# KDWM1000_Sch.net
KiCad netlist of a schematic drawn in Altium Designer
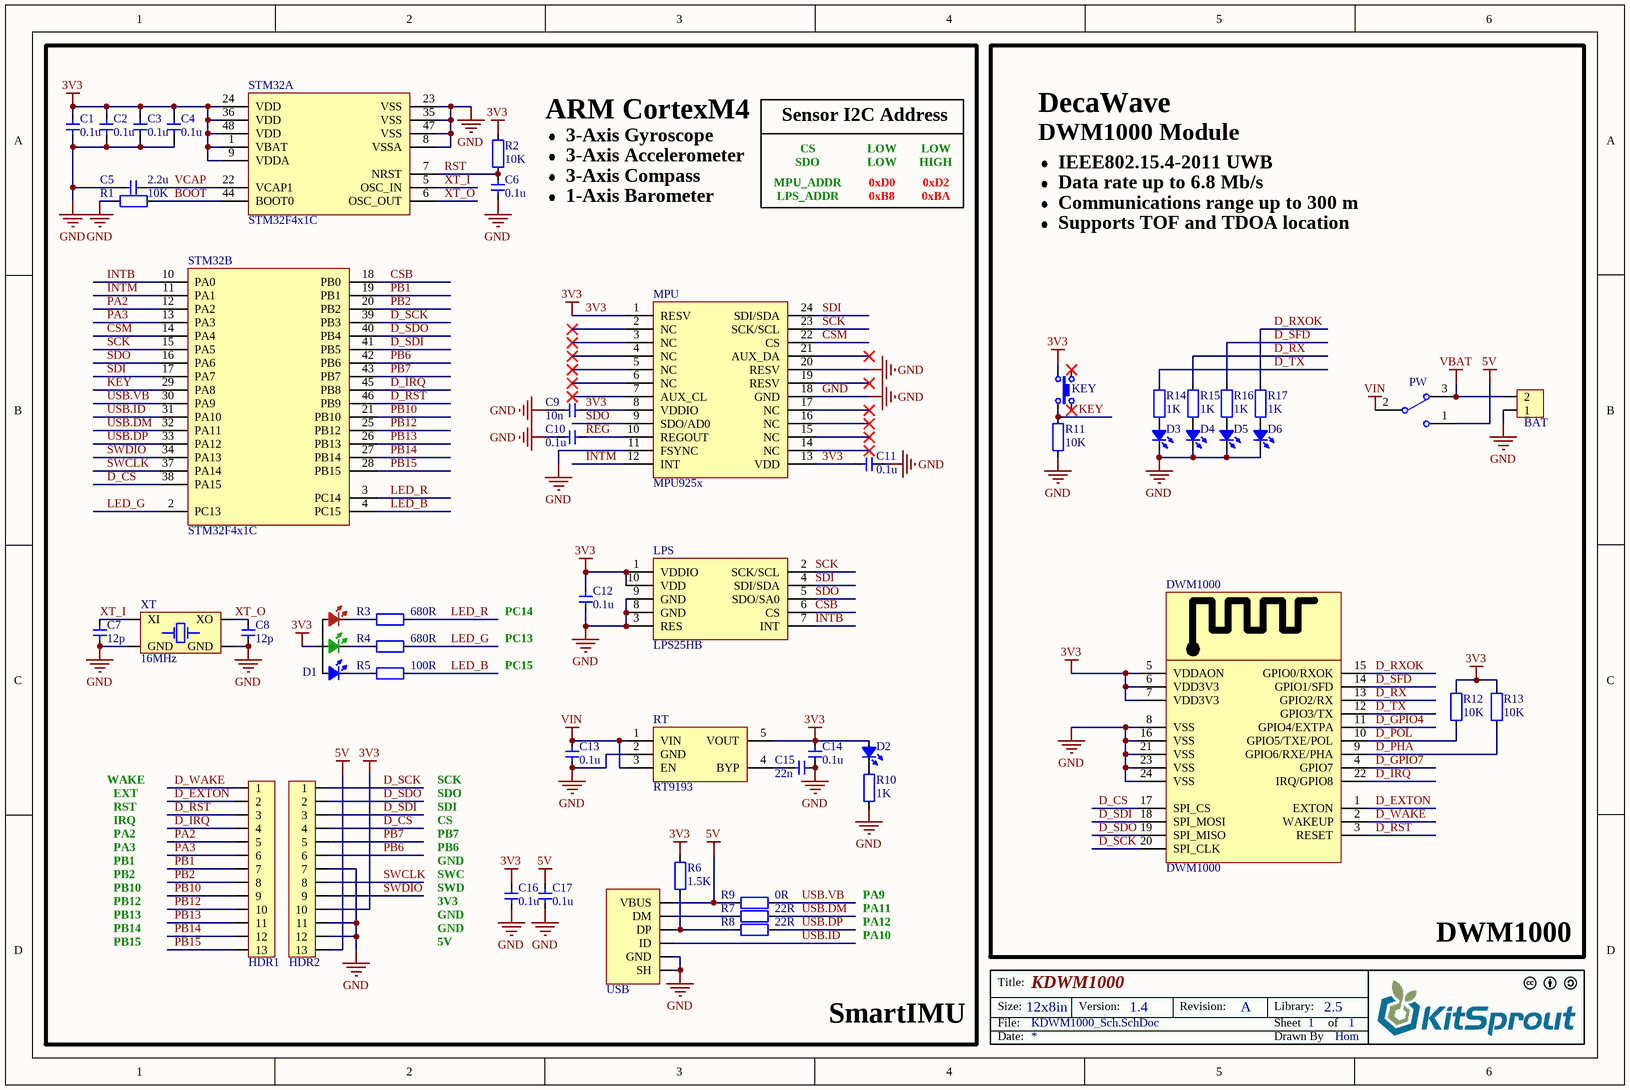
[diagram p0: KDWM1000_Sch.SchDoc]

(export (version "E")
  (design (tool "Eeschema 10.0.6"))
  (components
    (comp (ref "BAT")
      (value "HDR1x2_2.54")
      (footprint "PCB_ConnectorHDR:HDR1X2_2.54_180HD")
      (description "Header")
      (libsource (lib "SCH_ConnectorHDR") (part "HDR1x2_2.54T"))
    )
    (comp (ref "C1")
      (value "0.1u")
      (footprint "PCB_PassiveCap:CAP_0402")
      (description "Capacitor")
      (fields (field (name "Comment") "Cap_0402"))
      (libsource (lib "SCH_Passive") (part "Cap_0402"))
    )
    (comp (ref "C2")
      (value "0.1u")
      (footprint "PCB_PassiveCap:CAP_0402")
      (description "Capacitor")
      (fields (field (name "Comment") "Cap_0402"))
      (libsource (lib "SCH_Passive") (part "Cap_0402"))
    )
    (comp (ref "C3")
      (value "0.1u")
      (footprint "PCB_PassiveCap:CAP_0402")
      (description "Capacitor")
      (fields (field (name "Comment") "Cap_0402"))
      (libsource (lib "SCH_Passive") (part "Cap_0402"))
    )
    (comp (ref "C4")
      (value "0.1u")
      (footprint "PCB_PassiveCap:CAP_0402")
      (description "Capacitor")
      (fields (field (name "Comment") "Cap_0402"))
      (libsource (lib "SCH_Passive") (part "Cap_0402"))
    )
    (comp (ref "C5")
      (value "2.2u")
      (footprint "PCB_PassiveCap:CAP_0402")
      (description "Capacitor")
      (fields (field (name "Comment") "Cap_0402"))
      (libsource (lib "SCH_Passive") (part "Cap_0402"))
    )
    (comp (ref "C6")
      (value "0.1u")
      (footprint "PCB_PassiveCap:CAP_0402")
      (description "Capacitor")
      (fields (field (name "Comment") "Cap_0402"))
      (libsource (lib "SCH_Passive") (part "Cap_0402"))
    )
    (comp (ref "C7")
      (value "12p")
      (footprint "PCB_PassiveCap:CAP_0402")
      (description "Capacitor")
      (fields (field (name "Comment") "Cap_0402"))
      (libsource (lib "SCH_Passive") (part "Cap_0402"))
    )
    (comp (ref "C8")
      (value "12p")
      (footprint "PCB_PassiveCap:CAP_0402")
      (description "Capacitor")
      (fields (field (name "Comment") "Cap_0402"))
      (libsource (lib "SCH_Passive") (part "Cap_0402"))
    )
    (comp (ref "C9")
      (value "10n")
      (footprint "PCB_PassiveCap:CAP_0402")
      (description "Capacitor")
      (fields (field (name "Comment") "Cap_0402"))
      (libsource (lib "SCH_Passive") (part "Cap_0402"))
    )
    (comp (ref "C10")
      (value "0.1u")
      (footprint "PCB_PassiveCap:CAP_0402")
      (description "Capacitor")
      (fields (field (name "Comment") "Cap_0402"))
      (libsource (lib "SCH_Passive") (part "Cap_0402"))
    )
    (comp (ref "C11")
      (value "0.1u")
      (footprint "PCB_PassiveCap:CAP_0402")
      (description "Capacitor")
      (fields (field (name "Comment") "Cap_0402"))
      (libsource (lib "SCH_Passive") (part "Cap_0402"))
    )
    (comp (ref "C12")
      (value "0.1u")
      (footprint "PCB_PassiveCap:CAP_0402")
      (description "Capacitor")
      (fields (field (name "Comment") "Cap_0402"))
      (libsource (lib "SCH_Passive") (part "Cap_0402"))
    )
    (comp (ref "C13")
      (value "0.1u")
      (footprint "PCB_PassiveCap:CAP_0603")
      (description "Capacitor")
      (fields (field (name "Comment") "Cap_0603"))
      (libsource (lib "SCH_Passive") (part "Cap_0603"))
    )
    (comp (ref "C14")
      (value "0.1u")
      (footprint "PCB_PassiveCap:CAP_0603")
      (description "Capacitor")
      (fields (field (name "Comment") "Cap_0603"))
      (libsource (lib "SCH_Passive") (part "Cap_0603"))
    )
    (comp (ref "C15")
      (value "22n")
      (footprint "PCB_PassiveCap:CAP_0603")
      (description "Capacitor")
      (fields (field (name "Comment") "Cap_0603"))
      (libsource (lib "SCH_Passive") (part "Cap_0603"))
    )
    (comp (ref "C16")
      (value "0.1u")
      (footprint "PCB_PassiveCap:CAP_0603")
      (description "Capacitor")
      (fields (field (name "Comment") "Cap_0603"))
      (libsource (lib "SCH_Passive") (part "Cap_0603"))
    )
    (comp (ref "C17")
      (value "0.1u")
      (footprint "PCB_PassiveCap:CAP_0603")
      (description "Capacitor")
      (fields (field (name "Comment") "Cap_0603"))
      (libsource (lib "SCH_Passive") (part "Cap_0603"))
    )
    (comp (ref "D1")
      (value "LED_1616_RGB")
      (footprint "PCB_ActiveLED:LED_1616_RGB")
      (description "LED")
      (libsource (lib "SCH_Active") (part "LED_1616_RGB"))
    )
    (comp (ref "D2")
      (value "LED_0603")
      (footprint "PCB_ActiveLED:LED_0603_YELLOW")
      (description "LED")
      (libsource (lib "SCH_Active") (part "LED_0603"))
    )
    (comp (ref "D3")
      (value "LED_0603")
      (footprint "PCB_ActiveLED:LED_0603_YELLOW")
      (description "LED")
      (libsource (lib "SCH_Active") (part "LED_0603"))
    )
    (comp (ref "D4")
      (value "LED_0603")
      (footprint "PCB_ActiveLED:LED_0603_YELLOW")
      (description "LED")
      (libsource (lib "SCH_Active") (part "LED_0603"))
    )
    (comp (ref "D5")
      (value "LED_0603")
      (footprint "PCB_ActiveLED:LED_0603_RED")
      (description "LED")
      (libsource (lib "SCH_Active") (part "LED_0603"))
    )
    (comp (ref "D6")
      (value "LED_0603")
      (footprint "PCB_ActiveLED:LED_0603_GREEN")
      (description "LED")
      (libsource (lib "SCH_Active") (part "LED_0603"))
    )
    (comp (ref "DWM1000")
      (value "DWM1000")
      (footprint "PCB_Module:DWM1000")
      (description "Module")
      (fields (field (name "MANUFACTURER") "Decawave Limited"))
      (libsource (lib "SCH_Module") (part "DWM1000"))
    )
    (comp (ref "HDR1")
      (value "HDR1x13_2.54")
      (footprint "PCB_ConnectorHDR:HDR1X13_2.54_180")
      (description "Header")
      (libsource (lib "SCH_ConnectorHDR") (part "HDR1x13_2.54"))
    )
    (comp (ref "HDR2")
      (value "HDR1x13_2.54T")
      (footprint "PCB_ConnectorHDR:HDR1X13_2.54_180")
      (description "Header")
      (libsource (lib "SCH_ConnectorHDR") (part "HDR1x13_2.54T"))
    )
    (comp (ref "KEY")
      (value "ButtonTACT")
      (footprint "PCB_Switch:ButtonTACT_3.5*3.55_90")
      (description "Button")
      (libsource (lib "SCH_Switch") (part "ButtonTACT"))
    )
    (comp (ref "LPS")
      (value "LPS25HB")
      (footprint "PCB_IntegratedCircuit:HCLGA-2.5x2.5_10")
      (description "Sensor Pressure")
      (libsource (lib "SCH_IntegratedCircuit") (part "LPS25Hx"))
    )
    (comp (ref "MPU")
      (value "MPU925x")
      (footprint "PCB_IntegratedCircuit:QFN_P0.4_24")
      (description "Sensor Motion")
      (libsource (lib "SCH_IntegratedCircuit") (part "MPU925x"))
    )
    (comp (ref "PW")
      (value "SwitchSPDT_2.8x6.6_90")
      (footprint "PCB_Switch:SwitchSPDT_2.8X6.6_90")
      (description "Switch")
      (libsource (lib "SCH_Switch") (part "SwitchSPDT_2.8x6.6_90"))
    )
    (comp (ref "R1")
      (value "10K")
      (footprint "PCB_PassiveRes:RES_0402")
      (description "Resistor")
      (fields (field (name "Comment") "Res_0402"))
      (libsource (lib "") (part "Res_0402_2"))
    )
    (comp (ref "R2")
      (value "10K")
      (footprint "PCB_PassiveRes:RES_0402")
      (description "Resistor")
      (fields (field (name "Comment") "Res_0402"))
      (libsource (lib "") (part "Res_0402_1"))
    )
    (comp (ref "R3")
      (value "680R")
      (footprint "PCB_PassiveRes:RES_0402")
      (description "Resistor")
      (fields (field (name "Comment") "Res_0402"))
      (libsource (lib "SCH_Passive") (part "Res_0402"))
    )
    (comp (ref "R4")
      (value "680R")
      (footprint "PCB_PassiveRes:RES_0402")
      (description "Resistor")
      (fields (field (name "Comment") "Res_0402"))
      (libsource (lib "SCH_Passive") (part "Res_0402"))
    )
    (comp (ref "R5")
      (value "100R")
      (footprint "PCB_PassiveRes:RES_0402")
      (description "Resistor")
      (fields (field (name "Comment") "Res_0402"))
      (libsource (lib "SCH_Passive") (part "Res_0402"))
    )
    (comp (ref "R6")
      (value "1.5K")
      (footprint "PCB_PassiveRes:RES_0603")
      (description "Resistor")
      (fields (field (name "Comment") "Res_0603"))
      (libsource (lib "") (part "Res_0603_2"))
    )
    (comp (ref "R7")
      (value "22R")
      (footprint "PCB_PassiveRes:RES_0603")
      (description "Resistor")
      (fields (field (name "Comment") "Res_0603"))
      (libsource (lib "SCH_Passive") (part "Res_0603"))
    )
    (comp (ref "R8")
      (value "22R")
      (footprint "PCB_PassiveRes:RES_0603")
      (description "Resistor")
      (fields (field (name "Comment") "Res_0603"))
      (libsource (lib "SCH_Passive") (part "Res_0603"))
    )
    (comp (ref "R9")
      (value "0R")
      (footprint "PCB_PassiveRes:RES_0603")
      (description "Resistor")
      (fields (field (name "Comment") "Res_0603"))
      (libsource (lib "") (part "Res_0603_3"))
    )
    (comp (ref "R10")
      (value "1K")
      (footprint "PCB_PassiveRes:RES_0603")
      (description "Resistor")
      (fields (field (name "Comment") "Res_0603"))
      (libsource (lib "") (part "Res_0603_1"))
    )
    (comp (ref "R11")
      (value "10K")
      (footprint "PCB_PassiveRes:RES_0603")
      (description "Resistor")
      (fields (field (name "Comment") "Res_0603"))
      (libsource (lib "") (part "Res_0603_1"))
    )
    (comp (ref "R12")
      (value "10K")
      (footprint "PCB_PassiveRes:RES_0603")
      (description "Resistor")
      (fields (field (name "Comment") "Res_0603"))
      (libsource (lib "") (part "Res_0603_1"))
    )
    (comp (ref "R13")
      (value "10K")
      (footprint "PCB_PassiveRes:RES_0603")
      (description "Resistor")
      (fields (field (name "Comment") "Res_0603"))
      (libsource (lib "") (part "Res_0603_1"))
    )
    (comp (ref "R14")
      (value "1K")
      (footprint "PCB_PassiveRes:RES_0603")
      (description "Resistor")
      (fields (field (name "Comment") "Res_0603"))
      (libsource (lib "") (part "Res_0603_1"))
    )
    (comp (ref "R15")
      (value "1K")
      (footprint "PCB_PassiveRes:RES_0603")
      (description "Resistor")
      (fields (field (name "Comment") "Res_0603"))
      (libsource (lib "") (part "Res_0603_1"))
    )
    (comp (ref "R16")
      (value "1K")
      (footprint "PCB_PassiveRes:RES_0603")
      (description "Resistor")
      (fields (field (name "Comment") "Res_0603"))
      (libsource (lib "") (part "Res_0603_1"))
    )
    (comp (ref "R17")
      (value "1K")
      (footprint "PCB_PassiveRes:RES_0603")
      (description "Resistor")
      (fields (field (name "Comment") "Res_0603"))
      (libsource (lib "") (part "Res_0603_1"))
    )
    (comp (ref "RT")
      (value "RT9193")
      (footprint "PCB_IntegratedCircuit:SOT23-5")
      (description "Power")
      (libsource (lib "SCH_IntegratedCircuit") (part "RT9193"))
    )
    (comp (ref "STM32")
      (value "STM32F4x1C")
      (footprint "PCB_IntegratedCircuit:QFN_P0.5_48")
      (description "MCU")
      (libsource (lib "SCH_IntegratedCircuit") (part "STM32F4x1C"))
    )
    (comp (ref "USB")
      (value "USB_Micro")
      (footprint "PCB_USB:USB_Micro-AB")
      (description "USB")
      (libsource (lib "SCH_USB") (part "USB_Micro"))
    )
    (comp (ref "XT")
      (value "16MHz")
      (footprint "PCB_Oscillator:XT_2520_4")
      (description "Crystal Oscillator")
      (fields (field (name "Comment") "XTAL_2520_4P"))
      (libsource (lib "SCH_Oscillator") (part "XTAL_2520_4P"))
    )
  )
  (nets
    (net (code "1") (name "/BOOT") (class "Default")
      (node (ref "R1") (pin "2") (pinfunction "2_2") (pintype "passive"))
      (node (ref "STM32") (pin "44") (pinfunction "BOOT0_44") (pintype "passive"))
    )
    (net (code "2") (name "/CSB") (class "Default")
      (node (ref "LPS") (pin "6") (pinfunction "CS_6") (pintype "passive"))
      (node (ref "STM32") (pin "18") (pinfunction "PB0_18") (pintype "passive"))
    )
    (net (code "3") (name "/CSM") (class "Default")
      (node (ref "MPU") (pin "22") (pinfunction "CS_22") (pintype "passive"))
      (node (ref "STM32") (pin "14") (pinfunction "PA4_14") (pintype "passive"))
    )
    (net (code "4") (name "/D_CS") (class "Default")
      (node (ref "DWM1000") (pin "17") (pinfunction "SPI_CS_17") (pintype "passive"))
      (node (ref "HDR2") (pin "4") (pinfunction "4_4") (pintype "passive"))
      (node (ref "STM32") (pin "38") (pinfunction "PA15_38") (pintype "passive"))
    )
    (net (code "5") (name "/D_EXTON") (class "Default")
      (node (ref "DWM1000") (pin "1") (pinfunction "EXTON_1") (pintype "passive"))
      (node (ref "HDR1") (pin "2") (pinfunction "2_2") (pintype "passive"))
    )
    (net (code "6") (name "/D_GPIO4") (class "Default")
      (node (ref "DWM1000") (pin "11") (pinfunction "GPIO4/EXTPA_11") (pintype "passive"))
    )
    (net (code "7") (name "/D_GPIO7") (class "Default")
      (node (ref "DWM1000") (pin "4") (pinfunction "GPIO7_4") (pintype "passive"))
    )
    (net (code "8") (name "/D_IRQ") (class "Default")
      (node (ref "DWM1000") (pin "22") (pinfunction "IRQ/GPIO8_22") (pintype "passive"))
      (node (ref "HDR1") (pin "4") (pinfunction "4_4") (pintype "passive"))
      (node (ref "STM32") (pin "45") (pinfunction "PB8_45") (pintype "passive"))
    )
    (net (code "9") (name "/D_PHA") (class "Default")
      (node (ref "DWM1000") (pin "9") (pinfunction "GPIO6/RXE/PHA_9") (pintype "passive"))
      (node (ref "R13") (pin "1") (pinfunction "1_1") (pintype "passive"))
    )
    (net (code "10") (name "/D_POL") (class "Default")
      (node (ref "DWM1000") (pin "10") (pinfunction "GPIO5/TXE/POL_10") (pintype "passive"))
      (node (ref "R12") (pin "1") (pinfunction "1_1") (pintype "passive"))
    )
    (net (code "11") (name "/D_RST") (class "Default")
      (node (ref "DWM1000") (pin "3") (pinfunction "RESET_3") (pintype "passive"))
      (node (ref "HDR1") (pin "3") (pinfunction "3_3") (pintype "passive"))
      (node (ref "STM32") (pin "46") (pinfunction "PB9_46") (pintype "passive"))
    )
    (net (code "12") (name "/D_RX") (class "Default")
      (node (ref "DWM1000") (pin "13") (pinfunction "GPIO2/RX_13") (pintype "passive"))
      (node (ref "R15") (pin "2") (pinfunction "2_2") (pintype "passive"))
    )
    (net (code "13") (name "/D_RXOK") (class "Default")
      (node (ref "DWM1000") (pin "15") (pinfunction "GPIO0/RXOK_15") (pintype "passive"))
      (node (ref "R17") (pin "2") (pinfunction "2_2") (pintype "passive"))
    )
    (net (code "14") (name "/D_SCK") (class "Default")
      (node (ref "DWM1000") (pin "20") (pinfunction "SPI_CLK_20") (pintype "passive"))
      (node (ref "HDR2") (pin "1") (pinfunction "1_1") (pintype "passive"))
      (node (ref "STM32") (pin "39") (pinfunction "PB3_39") (pintype "passive"))
    )
    (net (code "15") (name "/D_SDI") (class "Default")
      (node (ref "DWM1000") (pin "18") (pinfunction "SPI_MOSI_18") (pintype "passive"))
      (node (ref "HDR2") (pin "3") (pinfunction "3_3") (pintype "passive"))
      (node (ref "STM32") (pin "41") (pinfunction "PB5_41") (pintype "passive"))
    )
    (net (code "16") (name "/D_SDO") (class "Default")
      (node (ref "DWM1000") (pin "19") (pinfunction "SPI_MISO_19") (pintype "passive"))
      (node (ref "HDR2") (pin "2") (pinfunction "2_2") (pintype "passive"))
      (node (ref "STM32") (pin "40") (pinfunction "PB4_40") (pintype "passive"))
    )
    (net (code "17") (name "/D_SFD") (class "Default")
      (node (ref "DWM1000") (pin "14") (pinfunction "GPIO1/SFD_14") (pintype "passive"))
      (node (ref "R16") (pin "2") (pinfunction "2_2") (pintype "passive"))
    )
    (net (code "18") (name "/D_TX") (class "Default")
      (node (ref "DWM1000") (pin "12") (pinfunction "GPIO3/TX_12") (pintype "passive"))
      (node (ref "R14") (pin "2") (pinfunction "2_2") (pintype "passive"))
    )
    (net (code "19") (name "/D_WAKE") (class "Default")
      (node (ref "DWM1000") (pin "2") (pinfunction "WAKEUP_2") (pintype "passive"))
      (node (ref "HDR1") (pin "1") (pinfunction "1_1") (pintype "passive"))
    )
    (net (code "20") (name "/INTB") (class "Default")
      (node (ref "LPS") (pin "7") (pinfunction "INT_7") (pintype "passive"))
      (node (ref "STM32") (pin "10") (pinfunction "PA0_10") (pintype "passive"))
    )
    (net (code "21") (name "/INTM") (class "Default")
      (node (ref "MPU") (pin "12") (pinfunction "INT_12") (pintype "passive"))
      (node (ref "STM32") (pin "11") (pinfunction "PA1_11") (pintype "passive"))
    )
    (net (code "22") (name "/KEY") (class "Default")
      (node (ref "KEY") (pin "4") (pinfunction "4_4") (pintype "passive"))
      (node (ref "R11") (pin "2") (pinfunction "2_2") (pintype "passive"))
      (node (ref "STM32") (pin "29") (pinfunction "PA8_29") (pintype "passive"))
    )
    (net (code "23") (name "/LED_B") (class "Default")
      (node (ref "R5") (pin "1") (pinfunction "1_1") (pintype "passive"))
      (node (ref "STM32") (pin "4") (pinfunction "PC15_4") (pintype "passive"))
    )
    (net (code "24") (name "/LED_G") (class "Default")
      (node (ref "R4") (pin "1") (pinfunction "1_1") (pintype "passive"))
      (node (ref "STM32") (pin "2") (pinfunction "PC13_2") (pintype "passive"))
    )
    (net (code "25") (name "/LED_R") (class "Default")
      (node (ref "R3") (pin "1") (pinfunction "1_1") (pintype "passive"))
      (node (ref "STM32") (pin "3") (pinfunction "PC14_3") (pintype "passive"))
    )
    (net (code "26") (name "/PA2") (class "Default")
      (node (ref "HDR1") (pin "5") (pinfunction "5_5") (pintype "passive"))
      (node (ref "STM32") (pin "12") (pinfunction "PA2_12") (pintype "passive"))
    )
    (net (code "27") (name "/PA3") (class "Default")
      (node (ref "HDR1") (pin "6") (pinfunction "6_6") (pintype "passive"))
      (node (ref "STM32") (pin "13") (pinfunction "PA3_13") (pintype "passive"))
    )
    (net (code "28") (name "/PB1") (class "Default")
      (node (ref "HDR1") (pin "7") (pinfunction "7_7") (pintype "passive"))
      (node (ref "STM32") (pin "19") (pinfunction "PB1_19") (pintype "passive"))
    )
    (net (code "29") (name "/PB2") (class "Default")
      (node (ref "HDR1") (pin "8") (pinfunction "8_8") (pintype "passive"))
      (node (ref "STM32") (pin "20") (pinfunction "PB2_20") (pintype "passive"))
    )
    (net (code "30") (name "/PB6") (class "Default")
      (node (ref "HDR2") (pin "6") (pinfunction "6_6") (pintype "passive"))
      (node (ref "STM32") (pin "42") (pinfunction "PB6_42") (pintype "passive"))
    )
    (net (code "31") (name "/PB7") (class "Default")
      (node (ref "HDR2") (pin "5") (pinfunction "5_5") (pintype "passive"))
      (node (ref "STM32") (pin "43") (pinfunction "PB7_43") (pintype "passive"))
    )
    (net (code "32") (name "/PB10") (class "Default")
      (node (ref "HDR1") (pin "9") (pinfunction "9_9") (pintype "passive"))
      (node (ref "STM32") (pin "21") (pinfunction "PB10_21") (pintype "passive"))
    )
    (net (code "33") (name "/PB12") (class "Default")
      (node (ref "HDR1") (pin "10") (pinfunction "10_10") (pintype "passive"))
      (node (ref "STM32") (pin "25") (pinfunction "PB12_25") (pintype "passive"))
    )
    (net (code "34") (name "/PB13") (class "Default")
      (node (ref "HDR1") (pin "11") (pinfunction "11_11") (pintype "passive"))
      (node (ref "STM32") (pin "26") (pinfunction "PB13_26") (pintype "passive"))
    )
    (net (code "35") (name "/PB14") (class "Default")
      (node (ref "HDR1") (pin "12") (pinfunction "12_12") (pintype "passive"))
      (node (ref "STM32") (pin "27") (pinfunction "PB14_27") (pintype "passive"))
    )
    (net (code "36") (name "/PB15") (class "Default")
      (node (ref "HDR1") (pin "13") (pinfunction "13_13") (pintype "passive"))
      (node (ref "STM32") (pin "28") (pinfunction "PB15_28") (pintype "passive"))
    )
    (net (code "37") (name "/REG") (class "Default")
      (node (ref "C10") (pin "1") (pinfunction "1_1") (pintype "passive"))
      (node (ref "MPU") (pin "10") (pinfunction "REGOUT_10") (pintype "passive"))
    )
    (net (code "38") (name "/RST") (class "Default")
      (node (ref "C6") (pin "1") (pinfunction "1_1") (pintype "passive"))
      (node (ref "R2") (pin "1") (pinfunction "1_1") (pintype "passive"))
      (node (ref "STM32") (pin "7") (pinfunction "NRST_7") (pintype "passive"))
    )
    (net (code "39") (name "/SCK") (class "Default")
      (node (ref "LPS") (pin "2") (pinfunction "SCK/SCL_2") (pintype "passive"))
      (node (ref "MPU") (pin "23") (pinfunction "SCK/SCL_23") (pintype "passive"))
      (node (ref "STM32") (pin "15") (pinfunction "PA5_15") (pintype "passive"))
    )
    (net (code "40") (name "/SDI") (class "Default")
      (node (ref "LPS") (pin "4") (pinfunction "SDI/SDA_4") (pintype "passive"))
      (node (ref "MPU") (pin "24") (pinfunction "SDI/SDA_24") (pintype "passive"))
      (node (ref "STM32") (pin "17") (pinfunction "PA7_17") (pintype "passive"))
    )
    (net (code "41") (name "/SDO") (class "Default")
      (node (ref "LPS") (pin "5") (pinfunction "SDO/SA0_5") (pintype "passive"))
      (node (ref "MPU") (pin "9") (pinfunction "SDO/AD0_9") (pintype "passive"))
      (node (ref "STM32") (pin "16") (pinfunction "PA6_16") (pintype "passive"))
    )
    (net (code "42") (name "/SWCLK") (class "Default")
      (node (ref "HDR2") (pin "8") (pinfunction "8_8") (pintype "passive"))
      (node (ref "STM32") (pin "37") (pinfunction "PA14_37") (pintype "passive"))
    )
    (net (code "43") (name "/SWDIO") (class "Default")
      (node (ref "HDR2") (pin "9") (pinfunction "9_9") (pintype "passive"))
      (node (ref "STM32") (pin "34") (pinfunction "PA13_34") (pintype "passive"))
    )
    (net (code "44") (name "/USB.DM") (class "Default")
      (node (ref "R7") (pin "2") (pinfunction "2_2") (pintype "passive"))
      (node (ref "STM32") (pin "32") (pinfunction "PA11_32") (pintype "passive"))
    )
    (net (code "45") (name "/USB.DP") (class "Default")
      (node (ref "R8") (pin "2") (pinfunction "2_2") (pintype "passive"))
      (node (ref "STM32") (pin "33") (pinfunction "PA12_33") (pintype "passive"))
    )
    (net (code "46") (name "/USB.ID") (class "Default")
      (node (ref "STM32") (pin "31") (pinfunction "PA10_31") (pintype "passive"))
      (node (ref "USB") (pin "4") (pinfunction "ID_4") (pintype "passive"))
    )
    (net (code "47") (name "/USB.VB") (class "Default")
      (node (ref "R9") (pin "1") (pinfunction "1_1") (pintype "passive"))
      (node (ref "STM32") (pin "30") (pinfunction "PA9_30") (pintype "passive"))
    )
    (net (code "48") (name "/VCAP") (class "Default")
      (node (ref "C5") (pin "2") (pinfunction "2_2") (pintype "passive"))
      (node (ref "STM32") (pin "22") (pinfunction "VCAP1_22") (pintype "passive"))
    )
    (net (code "49") (name "/XT_I") (class "Default")
      (node (ref "C7") (pin "2") (pinfunction "2_2") (pintype "passive"))
      (node (ref "STM32") (pin "5") (pinfunction "OSC_IN_5") (pintype "passive"))
      (node (ref "XT") (pin "1") (pinfunction "XI_1") (pintype "passive"))
    )
    (net (code "50") (name "/XT_O") (class "Default")
      (node (ref "C8") (pin "2") (pinfunction "2_2") (pintype "passive"))
      (node (ref "STM32") (pin "6") (pinfunction "OSC_OUT_6") (pintype "passive"))
      (node (ref "XT") (pin "3") (pinfunction "XO_3") (pintype "passive"))
    )
    (net (code "51") (name "3V3") (class "Default")
      (node (ref "C1") (pin "2") (pinfunction "2_2") (pintype "passive"))
      (node (ref "C11") (pin "2") (pinfunction "2_2") (pintype "passive"))
      (node (ref "C12") (pin "1") (pinfunction "1_1") (pintype "passive"))
      (node (ref "C14") (pin "2") (pinfunction "2_2") (pintype "passive"))
      (node (ref "C16") (pin "1") (pinfunction "1_1") (pintype "passive"))
      (node (ref "C2") (pin "2") (pinfunction "2_2") (pintype "passive"))
      (node (ref "C3") (pin "2") (pinfunction "2_2") (pintype "passive"))
      (node (ref "C4") (pin "2") (pinfunction "2_2") (pintype "passive"))
      (node (ref "C9") (pin "1") (pinfunction "1_1") (pintype "passive"))
      (node (ref "D1") (pin "4") (pinfunction "A_4") (pintype "passive"))
      (node (ref "D2") (pin "1") (pinfunction "A_1") (pintype "passive"))
      (node (ref "DWM1000") (pin "5") (pinfunction "VDDAON_5") (pintype "passive"))
      (node (ref "DWM1000") (pin "6") (pinfunction "VDD3V3_6") (pintype "passive"))
      (node (ref "DWM1000") (pin "7") (pinfunction "VDD3V3_7") (pintype "passive"))
      (node (ref "HDR2") (pin "10") (pinfunction "10_10") (pintype "passive"))
      (node (ref "KEY") (pin "3") (pinfunction "3_3") (pintype "passive"))
      (node (ref "LPS") (pin "1") (pinfunction "VDDIO_1") (pintype "passive"))
      (node (ref "LPS") (pin "10") (pinfunction "VDD_10") (pintype "passive"))
      (node (ref "MPU") (pin "1") (pinfunction "RESV_1") (pintype "passive"))
      (node (ref "MPU") (pin "13") (pinfunction "VDD_13") (pintype "passive"))
      (node (ref "MPU") (pin "8") (pinfunction "VDDIO_8") (pintype "passive"))
      (node (ref "R12") (pin "2") (pinfunction "2_2") (pintype "passive"))
      (node (ref "R13") (pin "2") (pinfunction "2_2") (pintype "passive"))
      (node (ref "R2") (pin "2") (pinfunction "2_2") (pintype "passive"))
      (node (ref "R6") (pin "1") (pinfunction "1_1") (pintype "passive"))
      (node (ref "RT") (pin "5") (pinfunction "VOUT_5") (pintype "passive"))
      (node (ref "STM32") (pin "1") (pinfunction "VBAT_1") (pintype "passive"))
      (node (ref "STM32") (pin "24") (pinfunction "VDD_24") (pintype "passive"))
      (node (ref "STM32") (pin "36") (pinfunction "VDD_36") (pintype "passive"))
      (node (ref "STM32") (pin "48") (pinfunction "VDD_48") (pintype "passive"))
      (node (ref "STM32") (pin "9") (pinfunction "VDDA_9") (pintype "passive"))
    )
    (net (code "52") (name "5V") (class "Default")
      (node (ref "C17") (pin "1") (pinfunction "1_1") (pintype "passive"))
      (node (ref "HDR2") (pin "13") (pinfunction "13_13") (pintype "passive"))
      (node (ref "PW") (pin "1") (pinfunction "1_1") (pintype "passive"))
      (node (ref "R9") (pin "2") (pinfunction "2_2") (pintype "passive"))
      (node (ref "USB") (pin "1") (pinfunction "VBUS_1") (pintype "passive"))
    )
    (net (code "53") (name "GND") (class "Default")
      (node (ref "BAT") (pin "1") (pinfunction "1_1") (pintype "passive"))
      (node (ref "C1") (pin "1") (pinfunction "1_1") (pintype "passive"))
      (node (ref "C10") (pin "2") (pinfunction "2_2") (pintype "passive"))
      (node (ref "C11") (pin "1") (pinfunction "1_1") (pintype "passive"))
      (node (ref "C12") (pin "2") (pinfunction "2_2") (pintype "passive"))
      (node (ref "C13") (pin "1") (pinfunction "1_1") (pintype "passive"))
      (node (ref "C14") (pin "1") (pinfunction "1_1") (pintype "passive"))
      (node (ref "C15") (pin "1") (pinfunction "1_1") (pintype "passive"))
      (node (ref "C16") (pin "2") (pinfunction "2_2") (pintype "passive"))
      (node (ref "C17") (pin "2") (pinfunction "2_2") (pintype "passive"))
      (node (ref "C2") (pin "1") (pinfunction "1_1") (pintype "passive"))
      (node (ref "C3") (pin "1") (pinfunction "1_1") (pintype "passive"))
      (node (ref "C4") (pin "1") (pinfunction "1_1") (pintype "passive"))
      (node (ref "C5") (pin "1") (pinfunction "1_1") (pintype "passive"))
      (node (ref "C6") (pin "2") (pinfunction "2_2") (pintype "passive"))
      (node (ref "C7") (pin "1") (pinfunction "1_1") (pintype "passive"))
      (node (ref "C8") (pin "1") (pinfunction "1_1") (pintype "passive"))
      (node (ref "C9") (pin "2") (pinfunction "2_2") (pintype "passive"))
      (node (ref "D3") (pin "2") (pinfunction "K_2") (pintype "passive"))
      (node (ref "D4") (pin "2") (pinfunction "K_2") (pintype "passive"))
      (node (ref "D5") (pin "2") (pinfunction "K_2") (pintype "passive"))
      (node (ref "D6") (pin "2") (pinfunction "K_2") (pintype "passive"))
      (node (ref "DWM1000") (pin "16") (pinfunction "VSS_16") (pintype "passive"))
      (node (ref "DWM1000") (pin "21") (pinfunction "VSS_21") (pintype "passive"))
      (node (ref "DWM1000") (pin "23") (pinfunction "VSS_23") (pintype "passive"))
      (node (ref "DWM1000") (pin "24") (pinfunction "VSS_24") (pintype "passive"))
      (node (ref "DWM1000") (pin "8") (pinfunction "VSS_8") (pintype "passive"))
      (node (ref "HDR2") (pin "11") (pinfunction "11_11") (pintype "passive"))
      (node (ref "HDR2") (pin "12") (pinfunction "12_12") (pintype "passive"))
      (node (ref "HDR2") (pin "7") (pinfunction "7_7") (pintype "passive"))
      (node (ref "LPS") (pin "3") (pinfunction "RES_3") (pintype "passive"))
      (node (ref "LPS") (pin "8") (pinfunction "GND_8") (pintype "passive"))
      (node (ref "LPS") (pin "9") (pinfunction "GND_9") (pintype "passive"))
      (node (ref "MPU") (pin "11") (pinfunction "FSYNC_11") (pintype "passive"))
      (node (ref "MPU") (pin "18") (pinfunction "GND_18") (pintype "passive"))
      (node (ref "MPU") (pin "20") (pinfunction "RESV_20") (pintype "passive"))
      (node (ref "R1") (pin "1") (pinfunction "1_1") (pintype "passive"))
      (node (ref "R10") (pin "1") (pinfunction "1_1") (pintype "passive"))
      (node (ref "R11") (pin "1") (pinfunction "1_1") (pintype "passive"))
      (node (ref "RT") (pin "2") (pinfunction "GND_2") (pintype "passive"))
      (node (ref "STM32") (pin "23") (pinfunction "VSS_23") (pintype "passive"))
      (node (ref "STM32") (pin "35") (pinfunction "VSS_35") (pintype "passive"))
      (node (ref "STM32") (pin "47") (pinfunction "VSS_47") (pintype "passive"))
      (node (ref "STM32") (pin "8") (pinfunction "VSSA_8") (pintype "passive"))
      (node (ref "USB") (pin "0") (pinfunction "SH_0") (pintype "passive"))
      (node (ref "USB") (pin "5") (pinfunction "GND_5") (pintype "passive"))
      (node (ref "XT") (pin "2") (pinfunction "GND_2") (pintype "passive"))
      (node (ref "XT") (pin "4") (pinfunction "GND_4") (pintype "passive"))
    )
    (net (code "54") (name "Net-(D1-B)") (class "Default")
      (node (ref "D1") (pin "3") (pinfunction "B_3") (pintype "passive"))
      (node (ref "R5") (pin "2") (pinfunction "2_2") (pintype "passive"))
    )
    (net (code "55") (name "Net-(D1-G)") (class "Default")
      (node (ref "D1") (pin "2") (pinfunction "G_2") (pintype "passive"))
      (node (ref "R4") (pin "2") (pinfunction "2_2") (pintype "passive"))
    )
    (net (code "56") (name "Net-(D1-R)") (class "Default")
      (node (ref "D1") (pin "1") (pinfunction "R_1") (pintype "passive"))
      (node (ref "R3") (pin "2") (pinfunction "2_2") (pintype "passive"))
    )
    (net (code "57") (name "Net-(D2-K)") (class "Default")
      (node (ref "D2") (pin "2") (pinfunction "K_2") (pintype "passive"))
      (node (ref "R10") (pin "2") (pinfunction "2_2") (pintype "passive"))
    )
    (net (code "58") (name "Net-(D3-A)") (class "Default")
      (node (ref "D3") (pin "1") (pinfunction "A_1") (pintype "passive"))
      (node (ref "R14") (pin "1") (pinfunction "1_1") (pintype "passive"))
    )
    (net (code "59") (name "Net-(D4-A)") (class "Default")
      (node (ref "D4") (pin "1") (pinfunction "A_1") (pintype "passive"))
      (node (ref "R15") (pin "1") (pinfunction "1_1") (pintype "passive"))
    )
    (net (code "60") (name "Net-(D5-A)") (class "Default")
      (node (ref "D5") (pin "1") (pinfunction "A_1") (pintype "passive"))
      (node (ref "R16") (pin "1") (pinfunction "1_1") (pintype "passive"))
    )
    (net (code "61") (name "Net-(D6-A)") (class "Default")
      (node (ref "D6") (pin "1") (pinfunction "A_1") (pintype "passive"))
      (node (ref "R17") (pin "1") (pinfunction "1_1") (pintype "passive"))
    )
    (net (code "62") (name "Net-(RT-BYP)") (class "Default")
      (node (ref "C15") (pin "2") (pinfunction "2_2") (pintype "passive"))
      (node (ref "RT") (pin "4") (pinfunction "BYP_4") (pintype "passive"))
    )
    (net (code "63") (name "Net-(USB-DM)") (class "Default")
      (node (ref "R7") (pin "1") (pinfunction "1_1") (pintype "passive"))
      (node (ref "USB") (pin "2") (pinfunction "DM_2") (pintype "passive"))
    )
    (net (code "64") (name "Net-(USB-DP)") (class "Default")
      (node (ref "R6") (pin "2") (pinfunction "2_2") (pintype "passive"))
      (node (ref "R8") (pin "1") (pinfunction "1_1") (pintype "passive"))
      (node (ref "USB") (pin "3") (pinfunction "DP_3") (pintype "passive"))
    )
    (net (code "65") (name "VBAT") (class "Default")
      (node (ref "BAT") (pin "2") (pinfunction "2_2") (pintype "passive"))
      (node (ref "PW") (pin "3") (pinfunction "3_3") (pintype "passive"))
    )
    (net (code "66") (name "VIN") (class "Default")
      (node (ref "C13") (pin "2") (pinfunction "2_2") (pintype "passive"))
      (node (ref "PW") (pin "2") (pinfunction "2_2") (pintype "passive"))
      (node (ref "RT") (pin "1") (pinfunction "VIN_1") (pintype "passive"))
      (node (ref "RT") (pin "3") (pinfunction "EN_3") (pintype "power_in"))
    )
    (net (code "67") (name "unconnected-(KEY-Pad1)") (class "Default")
      (node (ref "KEY") (pin "1") (pinfunction "1_1") (pintype "passive+no_connect"))
    )
    (net (code "68") (name "unconnected-(KEY-Pad2)") (class "Default")
      (node (ref "KEY") (pin "2") (pinfunction "2_2") (pintype "passive+no_connect"))
    )
    (net (code "69") (name "unconnected-(MPU-AUX_CL-Pad7)") (class "Default")
      (node (ref "MPU") (pin "7") (pinfunction "AUX_CL_7") (pintype "passive+no_connect"))
    )
    (net (code "70") (name "unconnected-(MPU-AUX_DA-Pad21)") (class "Default")
      (node (ref "MPU") (pin "21") (pinfunction "AUX_DA_21") (pintype "passive+no_connect"))
    )
    (net (code "71") (name "unconnected-(MPU-NC-Pad2)") (class "Default")
      (node (ref "MPU") (pin "2") (pinfunction "NC_2") (pintype "passive+no_connect"))
    )
    (net (code "72") (name "unconnected-(MPU-NC-Pad3)") (class "Default")
      (node (ref "MPU") (pin "3") (pinfunction "NC_3") (pintype "passive+no_connect"))
    )
    (net (code "73") (name "unconnected-(MPU-NC-Pad4)") (class "Default")
      (node (ref "MPU") (pin "4") (pinfunction "NC_4") (pintype "passive+no_connect"))
    )
    (net (code "74") (name "unconnected-(MPU-NC-Pad5)") (class "Default")
      (node (ref "MPU") (pin "5") (pinfunction "NC_5") (pintype "passive+no_connect"))
    )
    (net (code "75") (name "unconnected-(MPU-NC-Pad6)") (class "Default")
      (node (ref "MPU") (pin "6") (pinfunction "NC_6") (pintype "passive+no_connect"))
    )
    (net (code "76") (name "unconnected-(MPU-NC-Pad14)") (class "Default")
      (node (ref "MPU") (pin "14") (pinfunction "NC_14") (pintype "passive+no_connect"))
    )
    (net (code "77") (name "unconnected-(MPU-NC-Pad15)") (class "Default")
      (node (ref "MPU") (pin "15") (pinfunction "NC_15") (pintype "passive+no_connect"))
    )
    (net (code "78") (name "unconnected-(MPU-NC-Pad16)") (class "Default")
      (node (ref "MPU") (pin "16") (pinfunction "NC_16") (pintype "passive+no_connect"))
    )
    (net (code "79") (name "unconnected-(MPU-NC-Pad17)") (class "Default")
      (node (ref "MPU") (pin "17") (pinfunction "NC_17") (pintype "passive+no_connect"))
    )
    (net (code "80") (name "unconnected-(MPU-RESV-Pad19)") (class "Default")
      (node (ref "MPU") (pin "19") (pinfunction "RESV_19") (pintype "passive+no_connect"))
    )
  )
)
